# Proc.net
KiCad netlist of a schematic drawn in Altium Designer
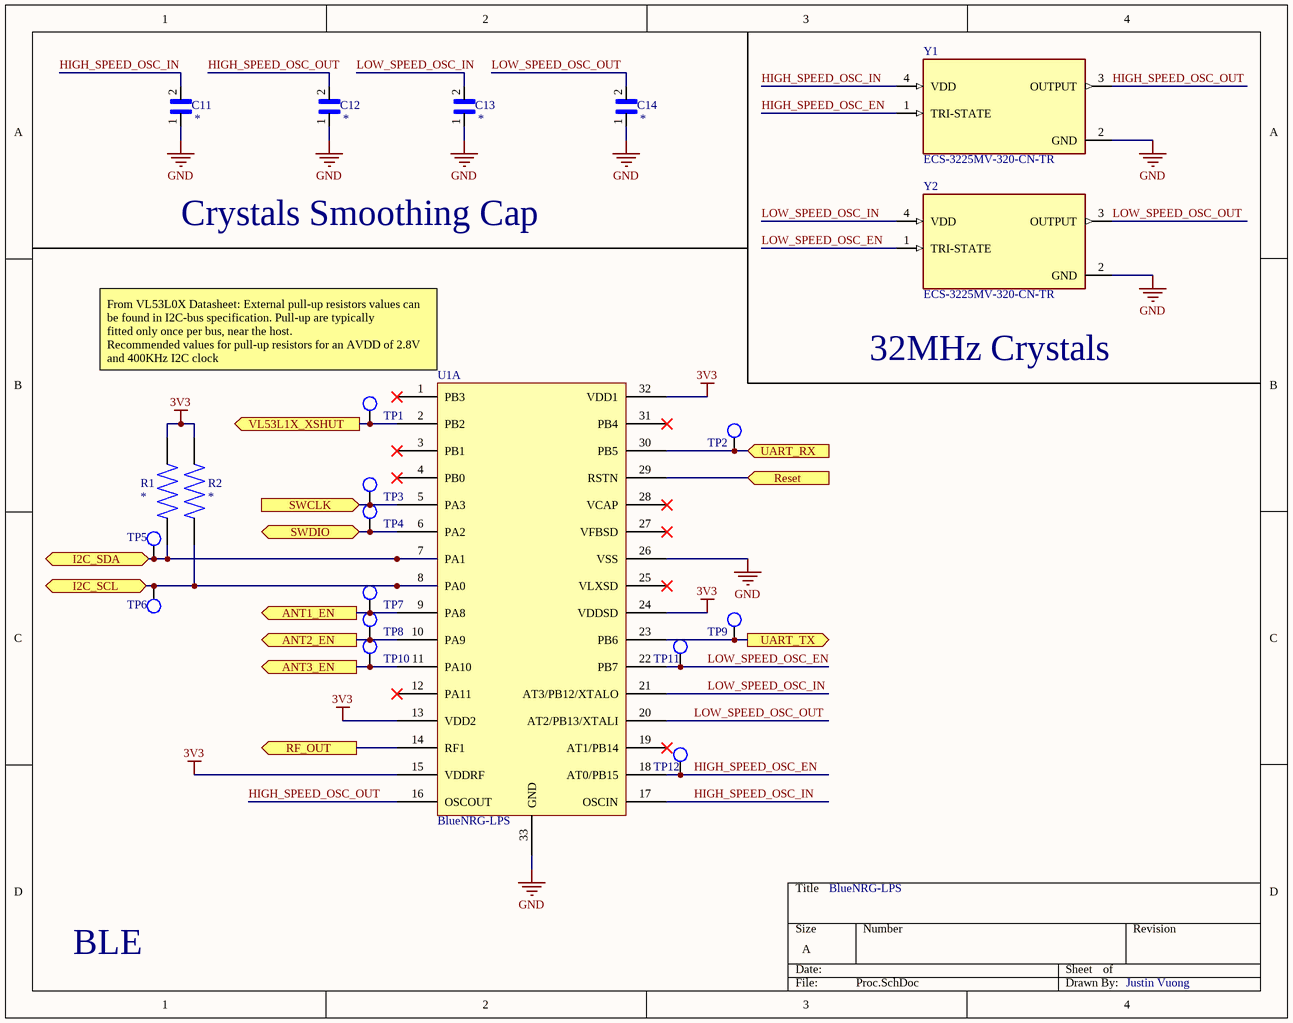
[diagram p0: Proc.SchDoc]

(export (version "E")
  (design (tool "Eeschema 10.0.6"))
  (components
    (comp (ref "C11")
      (value "04025A8R2CAT2A")
      (footprint "04025A8R2CAT2A:CAPC1005X56N")
      (description "0402 8,2 pF 50 V Â± 0,25 pF TolÃ©rance C0G / NP0 Condensateur cÃ©ramique multicouche SMT")
      (fields
        (field (name "DIGI-KEY_PART_NUMBER") "478-1069-1-ND")
        (field (name "MF") "AVX")
        (field (name "ALTIUM_VALUE") "*")
      )
      (libsource (lib "04025A8R2CAT2A") (part "04025A8R2CAT2A"))
    )
    (comp (ref "C12")
      (value "04025A8R2CAT2A")
      (footprint "04025A8R2CAT2A:CAPC1005X56N")
      (description "0402 8,2 pF 50 V Â± 0,25 pF TolÃ©rance C0G / NP0 Condensateur cÃ©ramique multicouche SMT")
      (fields
        (field (name "DIGI-KEY_PART_NUMBER") "478-1069-1-ND")
        (field (name "MF") "AVX")
        (field (name "ALTIUM_VALUE") "*")
      )
      (libsource (lib "04025A8R2CAT2A") (part "04025A8R2CAT2A"))
    )
    (comp (ref "C13")
      (value "04025A8R2CAT2A")
      (footprint "04025A8R2CAT2A:CAPC1005X56N")
      (description "0402 8,2 pF 50 V Â± 0,25 pF TolÃ©rance C0G / NP0 Condensateur cÃ©ramique multicouche SMT")
      (fields
        (field (name "DIGI-KEY_PART_NUMBER") "478-1069-1-ND")
        (field (name "MF") "AVX")
        (field (name "ALTIUM_VALUE") "*")
      )
      (libsource (lib "04025A8R2CAT2A") (part "04025A8R2CAT2A"))
    )
    (comp (ref "C14")
      (value "04025A8R2CAT2A")
      (footprint "04025A8R2CAT2A:CAPC1005X56N")
      (description "0402 8,2 pF 50 V Â± 0,25 pF TolÃ©rance C0G / NP0 Condensateur cÃ©ramique multicouche SMT")
      (fields
        (field (name "DIGI-KEY_PART_NUMBER") "478-1069-1-ND")
        (field (name "MF") "AVX")
        (field (name "ALTIUM_VALUE") "*")
      )
      (libsource (lib "04025A8R2CAT2A") (part "04025A8R2CAT2A"))
    )
    (comp (ref "R1")
      (value "RC0402JR-072KL")
      (footprint "RESC1005X40N")
      (description "2 kOhms Â±5% 0.063W, 1/16W Chip Resistor 0402 (1005 Metric) Moisture Resistant Thick Film")
      (fields
        (field (name "DIGIKEY_PART_NUMBER") "311-2.0KJRTR-ND")
        (field (name "MF") "Yageo")
        (field (name "ALTIUM_VALUE") "*")
      )
      (libsource (lib "RC0402JR-072KL") (part "RC0402JR-072KL"))
    )
    (comp (ref "R2")
      (value "RC0402JR-072KL")
      (footprint "RESC1005X40N")
      (description "2 kOhms Â±5% 0.063W, 1/16W Chip Resistor 0402 (1005 Metric) Moisture Resistant Thick Film")
      (fields
        (field (name "DIGIKEY_PART_NUMBER") "311-2.0KJRTR-ND")
        (field (name "MF") "Yageo")
        (field (name "ALTIUM_VALUE") "*")
      )
      (libsource (lib "RC0402JR-072KL") (part "RC0402JR-072KL"))
    )
    (comp (ref "TP1")
      (value "TESTPOINT_LOOP")
      (footprint "PCBComponent_1")
      (description "PC TEST POINT MINIATURE WHITE")
      (libsource (lib "Connectors and Headers") (part "TESTPOINT_LOOP"))
    )
    (comp (ref "TP2")
      (value "TESTPOINT_LOOP")
      (footprint "PCBComponent_1")
      (description "PC TEST POINT MINIATURE WHITE")
      (libsource (lib "Connectors and Headers") (part "TESTPOINT_LOOP"))
    )
    (comp (ref "TP3")
      (value "TESTPOINT_LOOP")
      (footprint "PCBComponent_1")
      (description "PC TEST POINT MINIATURE WHITE")
      (libsource (lib "Connectors and Headers") (part "TESTPOINT_LOOP"))
    )
    (comp (ref "TP4")
      (value "TESTPOINT_LOOP")
      (footprint "PCBComponent_1")
      (description "PC TEST POINT MINIATURE WHITE")
      (libsource (lib "Connectors and Headers") (part "TESTPOINT_LOOP"))
    )
    (comp (ref "TP5")
      (value "TESTPOINT_LOOP")
      (footprint "PCBComponent_1")
      (description "PC TEST POINT MINIATURE WHITE")
      (libsource (lib "Connectors and Headers") (part "TESTPOINT_LOOP"))
    )
    (comp (ref "TP6")
      (value "TESTPOINT_LOOP")
      (footprint "PCBComponent_1")
      (description "PC TEST POINT MINIATURE WHITE")
      (libsource (lib "Connectors and Headers") (part "TESTPOINT_LOOP"))
    )
    (comp (ref "TP7")
      (value "TESTPOINT_LOOP")
      (footprint "PCBComponent_1")
      (description "PC TEST POINT MINIATURE WHITE")
      (libsource (lib "Connectors and Headers") (part "TESTPOINT_LOOP"))
    )
    (comp (ref "TP8")
      (value "TESTPOINT_LOOP")
      (footprint "PCBComponent_1")
      (description "PC TEST POINT MINIATURE WHITE")
      (libsource (lib "Connectors and Headers") (part "TESTPOINT_LOOP"))
    )
    (comp (ref "TP9")
      (value "TESTPOINT_LOOP")
      (footprint "PCBComponent_1")
      (description "PC TEST POINT MINIATURE WHITE")
      (libsource (lib "Connectors and Headers") (part "TESTPOINT_LOOP"))
    )
    (comp (ref "TP10")
      (value "TESTPOINT_LOOP")
      (footprint "PCBComponent_1")
      (description "PC TEST POINT MINIATURE WHITE")
      (libsource (lib "Connectors and Headers") (part "TESTPOINT_LOOP"))
    )
    (comp (ref "TP11")
      (value "TESTPOINT_LOOP")
      (footprint "PCBComponent_1")
      (description "PC TEST POINT MINIATURE WHITE")
      (libsource (lib "Connectors and Headers") (part "TESTPOINT_LOOP"))
    )
    (comp (ref "TP12")
      (value "TESTPOINT_LOOP")
      (footprint "PCBComponent_1")
      (description "PC TEST POINT MINIATURE WHITE")
      (libsource (lib "Connectors and Headers") (part "TESTPOINT_LOOP"))
    )
    (comp (ref "U1")
      (value "BlueNRG-LPS")
      (footprint "VFQFPN32-5x5mm-M")
      (description "IC RF TxRx + MCU Bluetooth Bluetooth v5.3 2.4GHz 32-VFQFN Exposed Pad")
      (libsource (lib "Presgo") (part "BlueNRG-LPS"))
    )
    (comp (ref "Y1")
      (value "ECS-3225MV-320-CN-TR")
      (footprint "OSC_ECS-2333-160-BN-TR:OSC_ECS-2333-160-BN-TR")
      (description "subminiature SMD oscillators.")
      (libsource (lib "ECS-3225MV-320-CN-TR") (part "ECS-3225MV-320-CN-TR"))
    )
    (comp (ref "Y2")
      (value "ECS-3225MV-320-CN-TR")
      (footprint "OSC_ECS-2333-160-BN-TR:OSC_ECS-2333-160-BN-TR")
      (description "subminiature SMD oscillators.")
      (libsource (lib "ECS-3225MV-320-CN-TR") (part "ECS-3225MV-320-CN-TR"))
    )
  )
  (nets
    (net (code "1") (name "/ANT1_EN") (class "Default")
      (node (ref "TP7") (pin "1") (pintype "passive"))
      (node (ref "U1") (pin "9") (pinfunction "PA8_9") (pintype "passive"))
    )
    (net (code "2") (name "/ANT2_EN") (class "Default")
      (node (ref "TP8") (pin "1") (pintype "passive"))
      (node (ref "U1") (pin "10") (pinfunction "PA9_10") (pintype "passive"))
    )
    (net (code "3") (name "/ANT3_EN") (class "Default")
      (node (ref "TP10") (pin "1") (pintype "passive"))
      (node (ref "U1") (pin "11") (pinfunction "PA10_11") (pintype "passive"))
    )
    (net (code "4") (name "/HIGH_SPEED_OSC_EN") (class "Default")
      (node (ref "TP12") (pin "1") (pintype "passive"))
      (node (ref "U1") (pin "18") (pinfunction "AT0/PB15_18") (pintype "passive"))
      (node (ref "Y1") (pin "1") (pinfunction "TRI-STATE_1") (pintype "input"))
    )
    (net (code "5") (name "/HIGH_SPEED_OSC_IN") (class "Default")
      (node (ref "C11") (pin "2") (pinfunction "2_2") (pintype "passive"))
      (node (ref "U1") (pin "17") (pinfunction "OSCIN_17") (pintype "passive"))
      (node (ref "Y1") (pin "4") (pinfunction "VDD_4") (pintype "input"))
    )
    (net (code "6") (name "/HIGH_SPEED_OSC_OUT") (class "Default")
      (node (ref "C12") (pin "2") (pinfunction "2_2") (pintype "passive"))
      (node (ref "U1") (pin "16") (pinfunction "OSCOUT_16") (pintype "passive"))
      (node (ref "Y1") (pin "3") (pinfunction "OUTPUT_3") (pintype "output"))
    )
    (net (code "7") (name "/I2C_SCL") (class "Default")
      (node (ref "R2") (pin "2") (pinfunction "2_2") (pintype "passive"))
      (node (ref "TP6") (pin "1") (pintype "passive"))
      (node (ref "U1") (pin "8") (pinfunction "PA0_8") (pintype "passive"))
    )
    (net (code "8") (name "/I2C_SDA") (class "Default")
      (node (ref "R1") (pin "1") (pinfunction "1_1") (pintype "passive"))
      (node (ref "TP5") (pin "1") (pintype "passive"))
      (node (ref "U1") (pin "7") (pinfunction "PA1_7") (pintype "passive"))
    )
    (net (code "9") (name "/LOW_SPEED_OSC_EN") (class "Default")
      (node (ref "TP11") (pin "1") (pintype "passive"))
      (node (ref "U1") (pin "22") (pinfunction "PB7_22") (pintype "passive"))
      (node (ref "Y2") (pin "1") (pinfunction "TRI-STATE_1") (pintype "input"))
    )
    (net (code "10") (name "/LOW_SPEED_OSC_IN") (class "Default")
      (node (ref "C13") (pin "2") (pinfunction "2_2") (pintype "passive"))
      (node (ref "U1") (pin "21") (pinfunction "AT3/PB12/XTALO_21") (pintype "passive"))
      (node (ref "Y2") (pin "4") (pinfunction "VDD_4") (pintype "input"))
    )
    (net (code "11") (name "/LOW_SPEED_OSC_OUT") (class "Default")
      (node (ref "C14") (pin "2") (pinfunction "2_2") (pintype "passive"))
      (node (ref "U1") (pin "20") (pinfunction "AT2/PB13/XTALI_20") (pintype "passive"))
      (node (ref "Y2") (pin "3") (pinfunction "OUTPUT_3") (pintype "output"))
    )
    (net (code "12") (name "/RF_OUT") (class "Default")
      (node (ref "U1") (pin "14") (pinfunction "RF1_14") (pintype "passive"))
    )
    (net (code "13") (name "/Reset") (class "Default")
      (node (ref "U1") (pin "29") (pinfunction "RSTN_29") (pintype "passive"))
    )
    (net (code "14") (name "/SWCLK") (class "Default")
      (node (ref "TP3") (pin "1") (pintype "passive"))
      (node (ref "U1") (pin "5") (pinfunction "PA3_5") (pintype "passive"))
    )
    (net (code "15") (name "/SWDIO") (class "Default")
      (node (ref "TP4") (pin "1") (pintype "passive"))
      (node (ref "U1") (pin "6") (pinfunction "PA2_6") (pintype "passive"))
    )
    (net (code "16") (name "/UART_RX") (class "Default")
      (node (ref "TP2") (pin "1") (pintype "passive"))
      (node (ref "U1") (pin "30") (pinfunction "PB5_30") (pintype "passive"))
    )
    (net (code "17") (name "/UART_TX") (class "Default")
      (node (ref "TP9") (pin "1") (pintype "passive"))
      (node (ref "U1") (pin "23") (pinfunction "PB6_23") (pintype "passive"))
    )
    (net (code "18") (name "/VL53L1X_XSHUT") (class "Default")
      (node (ref "TP1") (pin "1") (pintype "passive"))
      (node (ref "U1") (pin "2") (pinfunction "PB2_2") (pintype "passive"))
    )
    (net (code "19") (name "3V3") (class "Default")
      (node (ref "R1") (pin "2") (pinfunction "2_2") (pintype "passive"))
      (node (ref "R2") (pin "1") (pinfunction "1_1") (pintype "passive"))
      (node (ref "U1") (pin "13") (pinfunction "VDD2_13") (pintype "passive"))
      (node (ref "U1") (pin "15") (pinfunction "VDDRF_15") (pintype "passive"))
      (node (ref "U1") (pin "24") (pinfunction "VDDSD_24") (pintype "passive"))
      (node (ref "U1") (pin "32") (pinfunction "VDD1_32") (pintype "passive"))
    )
    (net (code "20") (name "GND") (class "Default")
      (node (ref "C11") (pin "1") (pinfunction "1_1") (pintype "passive"))
      (node (ref "C12") (pin "1") (pinfunction "1_1") (pintype "passive"))
      (node (ref "C13") (pin "1") (pinfunction "1_1") (pintype "passive"))
      (node (ref "C14") (pin "1") (pinfunction "1_1") (pintype "passive"))
      (node (ref "U1") (pin "26") (pinfunction "VSS_26") (pintype "passive"))
      (node (ref "U1") (pin "33") (pinfunction "GND_33") (pintype "passive"))
      (node (ref "Y1") (pin "2") (pinfunction "GND_2") (pintype "power_in"))
      (node (ref "Y2") (pin "2") (pinfunction "GND_2") (pintype "power_in"))
    )
    (net (code "21") (name "unconnected-(U1-AT1{slash}PB14-Pad19)") (class "Default")
      (node (ref "U1") (pin "19") (pinfunction "AT1/PB14_19") (pintype "passive+no_connect"))
    )
    (net (code "22") (name "unconnected-(U1-PA11-Pad12)") (class "Default")
      (node (ref "U1") (pin "12") (pinfunction "PA11_12") (pintype "passive+no_connect"))
    )
    (net (code "23") (name "unconnected-(U1-PB0-Pad4)") (class "Default")
      (node (ref "U1") (pin "4") (pinfunction "PB0_4") (pintype "passive+no_connect"))
    )
    (net (code "24") (name "unconnected-(U1-PB1-Pad3)") (class "Default")
      (node (ref "U1") (pin "3") (pinfunction "PB1_3") (pintype "passive+no_connect"))
    )
    (net (code "25") (name "unconnected-(U1-PB3-Pad1)") (class "Default")
      (node (ref "U1") (pin "1") (pinfunction "PB3_1") (pintype "passive+no_connect"))
    )
    (net (code "26") (name "unconnected-(U1-PB4-Pad31)") (class "Default")
      (node (ref "U1") (pin "31") (pinfunction "PB4_31") (pintype "passive+no_connect"))
    )
    (net (code "27") (name "unconnected-(U1-VCAP-Pad28)") (class "Default")
      (node (ref "U1") (pin "28") (pinfunction "VCAP_28") (pintype "passive+no_connect"))
    )
    (net (code "28") (name "unconnected-(U1-VFBSD-Pad27)") (class "Default")
      (node (ref "U1") (pin "27") (pinfunction "VFBSD_27") (pintype "passive+no_connect"))
    )
    (net (code "29") (name "unconnected-(U1-VLXSD-Pad25)") (class "Default")
      (node (ref "U1") (pin "25") (pinfunction "VLXSD_25") (pintype "passive+no_connect"))
    )
  )
)
